# SCH_motorcontroller_2025-02-14.net
KiCad netlist of a schematic drawn in EasyEDA
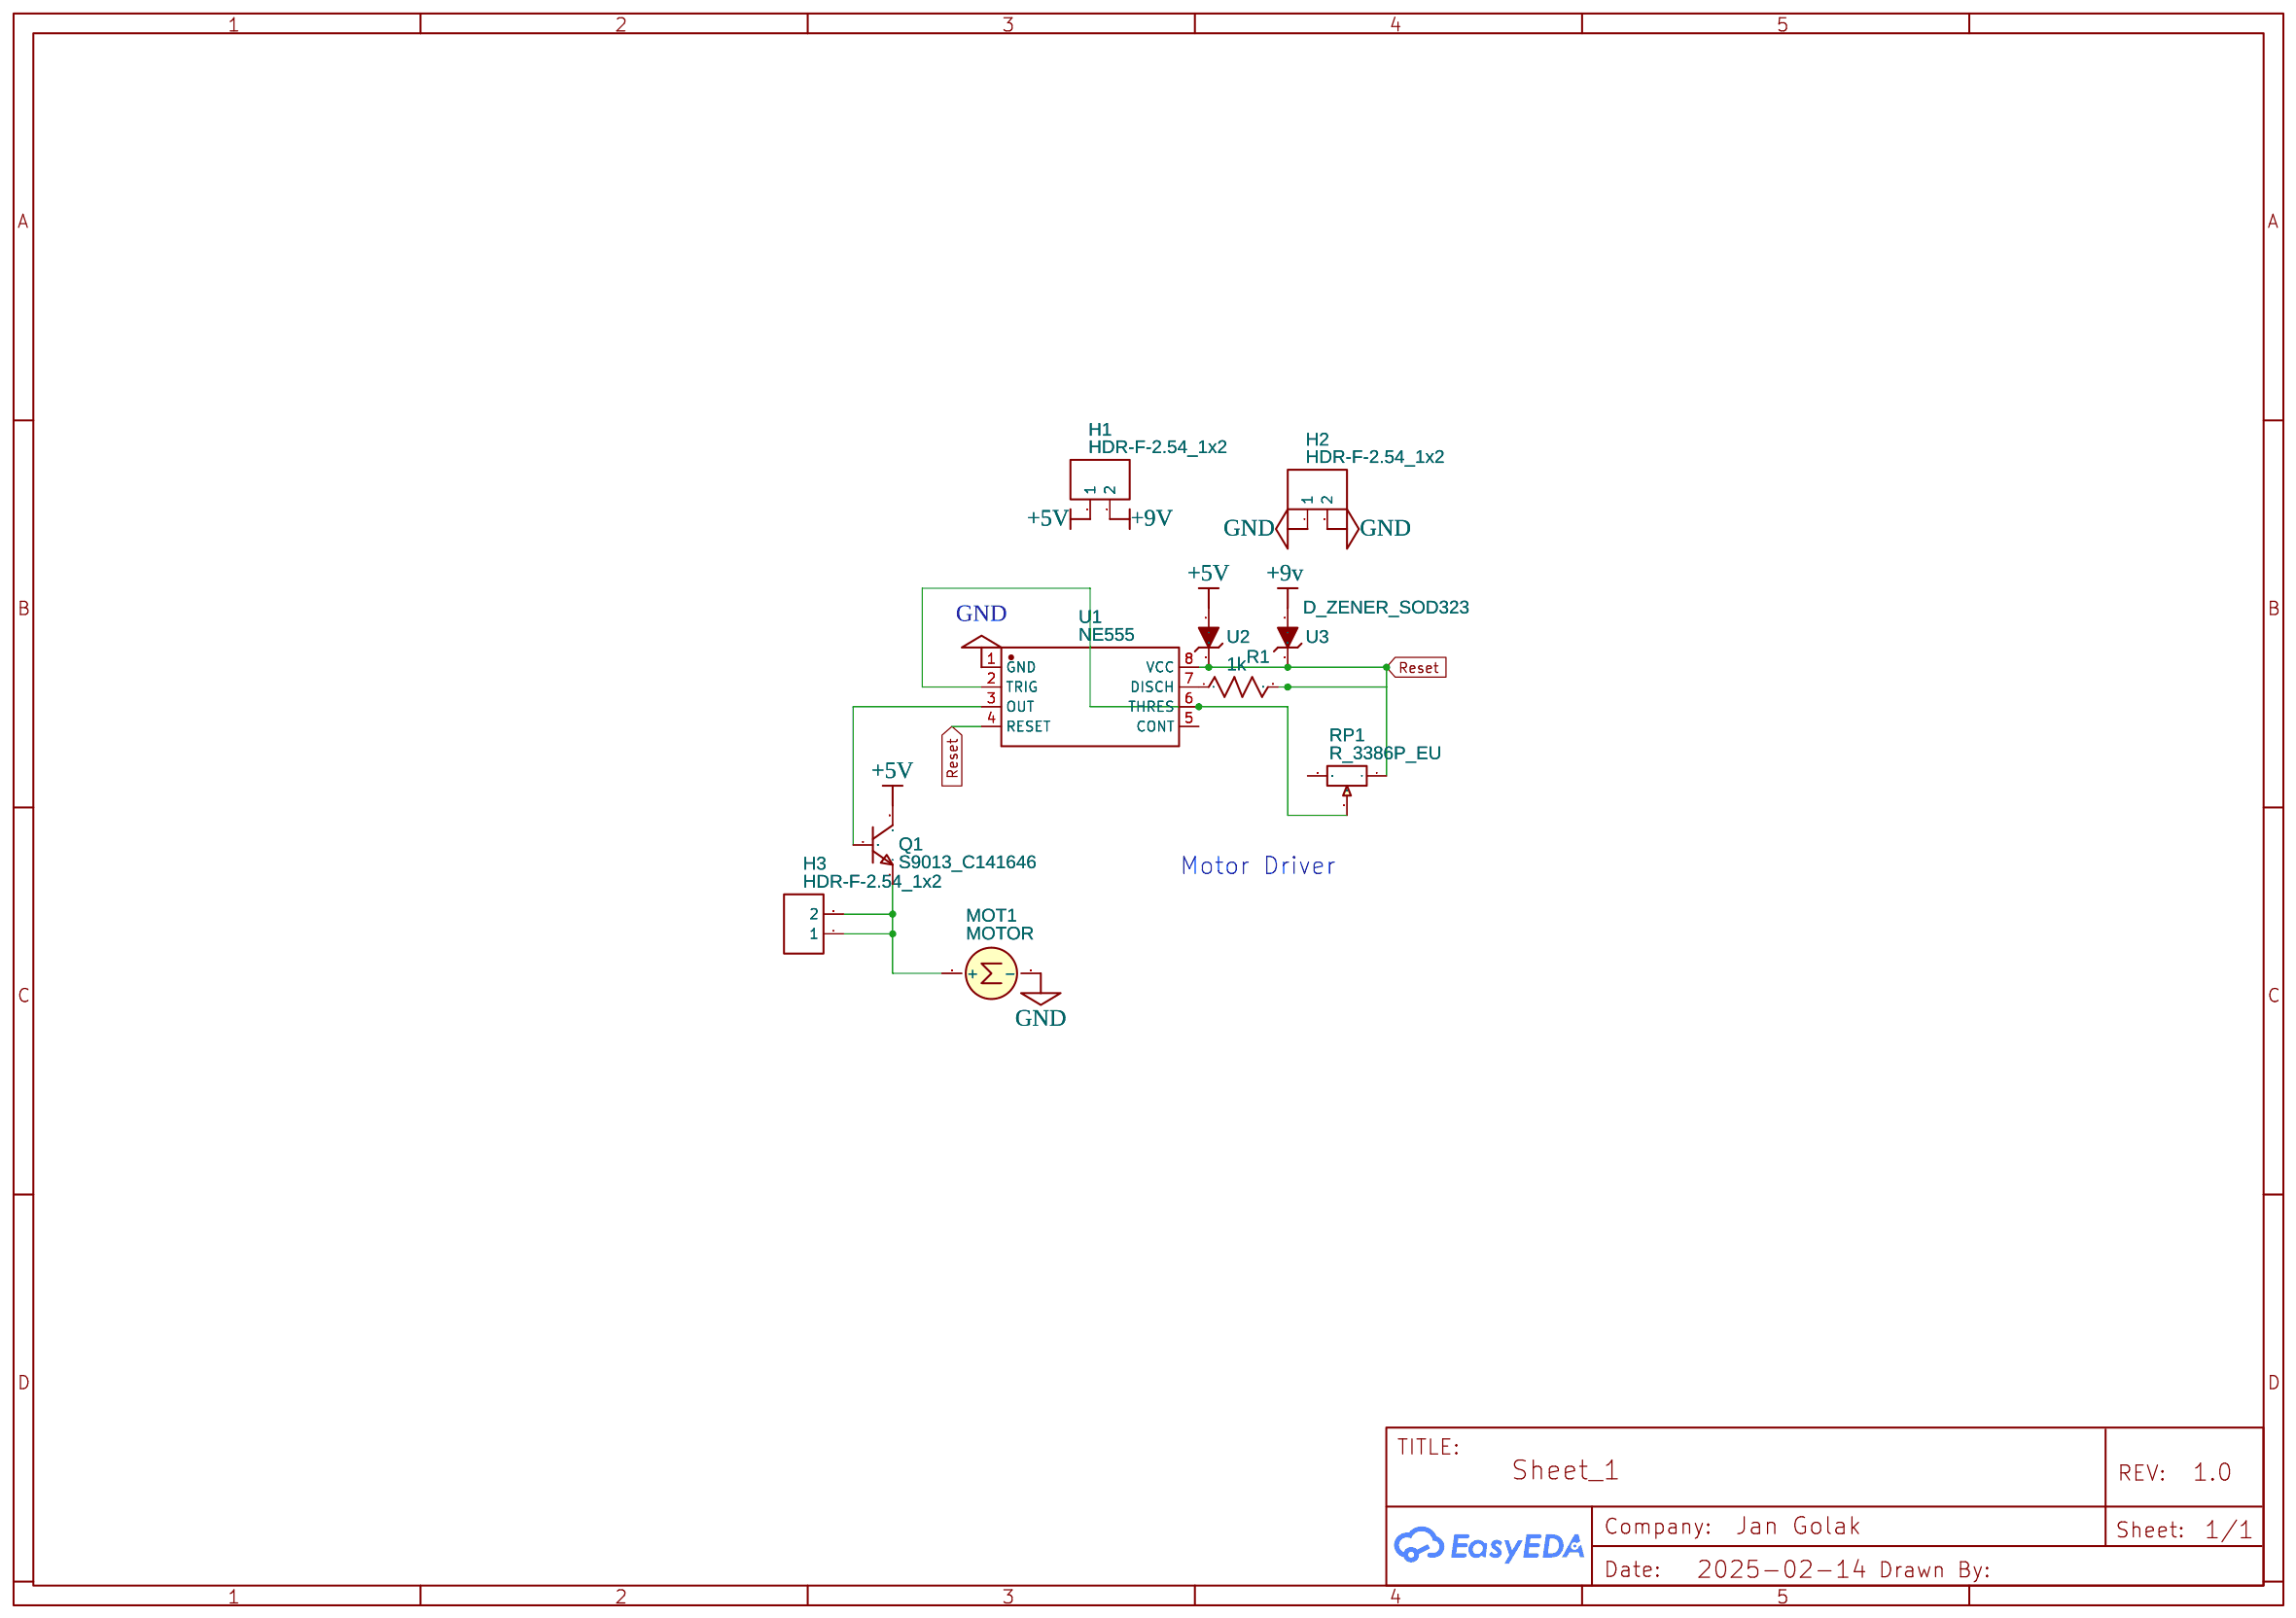
[diagram p0: schematic sheet]

(export (version "E")
  (design (tool "Eeschema 10.0.6"))
  (components
    (comp (ref "H1") (value "HDR-F-2.54_1x2") (libsource (lib "") (part "HDR-F-2.54_1x2")))
    (comp (ref "H2") (value "HDR-F-2.54_1x2") (libsource (lib "") (part "HDR-F-2.54_1x2")))
    (comp (ref "H3") (value "HDR-F-2.54_1x2") (libsource (lib "") (part "HDR-F-2.54_1x2_1")))
    (comp (ref "MOT1")
      (value "MOTOR")
      (fields (field (name "Manufacturer Part") "LCM1027A2445F") (field (name "Manufacturer") "LEADER(立得)"))
      (libsource (lib "") (part "motor 24v"))
    )
    (comp (ref "Q1")
      (value "S9013_C141646")
      (fields
        (field (name "Manufacturer Part") "S9013")
        (field (name "Manufacturer") "Changjiang Electronics Tech (CJ)")
      )
      (libsource (lib "") (part "S9013_C141646"))
    )
    (comp (ref "R1") (value "1k") (libsource (lib "") (part "R_0603_US")))
    (comp (ref "RP1") (value "R_3386P_EU") (libsource (lib "") (part "R_3386P_EU")))
    (comp (ref "U1") (value "NE555") (libsource (lib "") (part "NE555")))
    (comp (ref "U2")
      (value "D_ZENER_SOD323")
      (fields (field (name "Manufacturer Part") "D_Zener_SOD323"))
      (libsource (lib "") (part "D_ZENER_SOD323"))
    )
    (comp (ref "U3")
      (value "D_ZENER_SOD323")
      (fields (field (name "Manufacturer Part") "D_Zener_SOD323"))
      (libsource (lib "") (part "D_ZENER_SOD323"))
    )
  )
  (nets
    (net (code "1") (name "+5V") (class "Default")
      (node (ref "H1") (pin "1") (pinfunction "1_1") (pintype "input"))
      (node (ref "Q1") (pin "3") (pinfunction "C_3") (pintype "unspecified"))
      (node (ref "U2") (pin "2") (pinfunction "A_2") (pintype "unspecified"))
    )
    (net (code "2") (name "+9V") (class "Default")
      (node (ref "H1") (pin "2") (pinfunction "2_2") (pintype "input"))
    )
    (net (code "3") (name "+9v") (class "Default")
      (node (ref "U3") (pin "2") (pinfunction "A_2") (pintype "unspecified"))
    )
    (net (code "4") (name "GND") (class "Default")
      (node (ref "H2") (pin "1") (pinfunction "1_1") (pintype "input"))
      (node (ref "H2") (pin "2") (pinfunction "2_2") (pintype "input"))
      (node (ref "MOT1") (pin "1") (pinfunction "-_1") (pintype "unspecified"))
      (node (ref "U1") (pin "1") (pinfunction "GND_1") (pintype "unspecified"))
    )
    (net (code "5") (name "Net-(MOT1-+)") (class "Default")
      (node (ref "H3") (pin "1") (pinfunction "1_1") (pintype "input"))
      (node (ref "H3") (pin "2") (pinfunction "2_2") (pintype "input"))
      (node (ref "MOT1") (pin "2") (pinfunction "+_2") (pintype "unspecified"))
      (node (ref "Q1") (pin "1") (pinfunction "E_1") (pintype "unspecified"))
    )
    (net (code "6") (name "Net-(Q1-B)") (class "Default")
      (node (ref "Q1") (pin "2") (pinfunction "B_2") (pintype "unspecified"))
      (node (ref "U1") (pin "3") (pinfunction "OUT_3") (pintype "unspecified"))
    )
    (net (code "7") (name "Net-(U1-DISCH)") (class "Default")
      (node (ref "R1") (pin "1") (pinfunction "1_1") (pintype "unspecified"))
      (node (ref "U1") (pin "7") (pinfunction "DISCH_7") (pintype "unspecified"))
    )
    (net (code "8") (name "Net-(U1-THRES)") (class "Default")
      (node (ref "RP1") (pin "2") (pinfunction "2_2") (pintype "input"))
      (node (ref "U1") (pin "2") (pinfunction "TRIG_2") (pintype "unspecified"))
      (node (ref "U1") (pin "6") (pinfunction "THRES_6") (pintype "unspecified"))
    )
    (net (code "9") (name "Reset") (class "Default")
      (node (ref "R1") (pin "2") (pinfunction "2_2") (pintype "unspecified"))
      (node (ref "RP1") (pin "1") (pinfunction "1_1") (pintype "input"))
      (node (ref "U1") (pin "4") (pinfunction "RESET_4") (pintype "unspecified"))
      (node (ref "U1") (pin "8") (pinfunction "VCC_8") (pintype "unspecified"))
      (node (ref "U2") (pin "1") (pinfunction "C_1") (pintype "unspecified"))
      (node (ref "U3") (pin "1") (pinfunction "C_1") (pintype "unspecified"))
    )
    (net (code "10") (name "unconnected-(RP1-Pad3)") (class "Default")
      (node (ref "RP1") (pin "3") (pinfunction "3_3") (pintype "input"))
    )
    (net (code "11") (name "unconnected-(U1-CONT-Pad5)") (class "Default")
      (node (ref "U1") (pin "5") (pinfunction "CONT_5") (pintype "unspecified"))
    )
  )
)
